# SCH_krunchcard_2025-07-20.net
KiCad netlist of a schematic drawn in EasyEDA
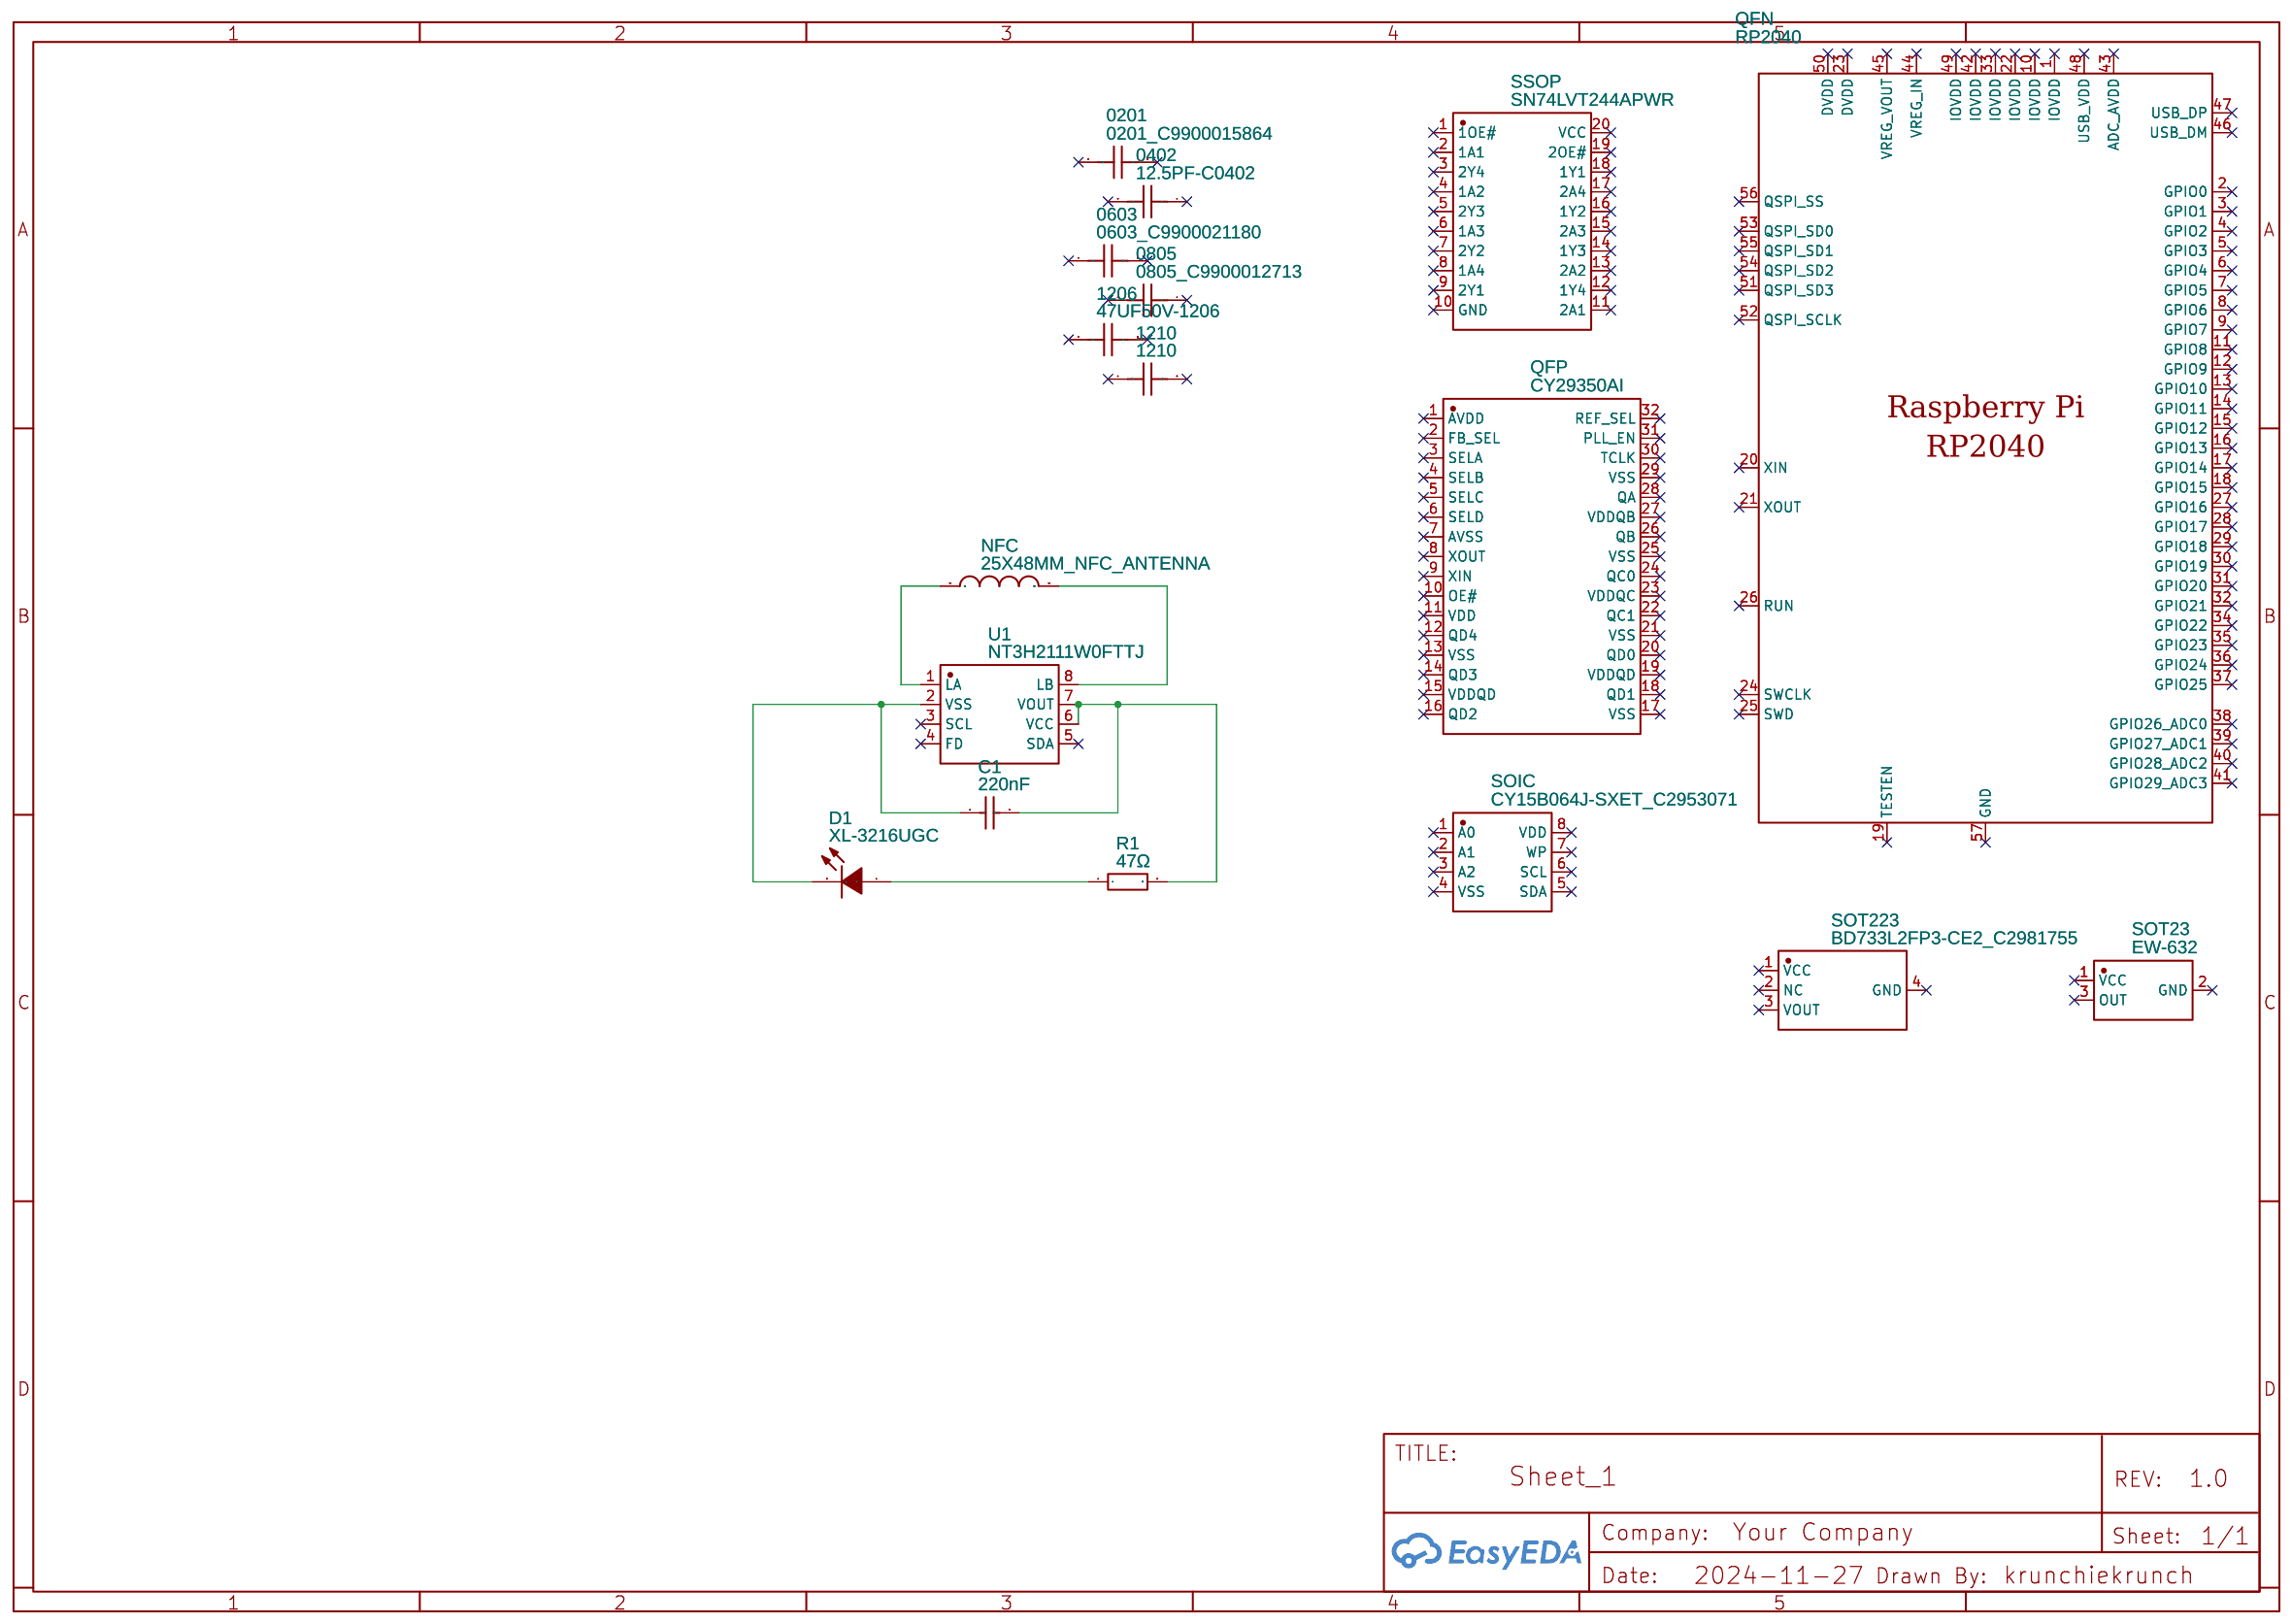
[diagram p0: schematic sheet]

(export (version "E")
  (design (tool "Eeschema 10.0.6"))
  (components
    (comp (ref "0201")
      (value "0201_C9900015864")
      (fields (field (name "Manufacturer Part") "0201"))
      (libsource (lib "") (part "0201_C9900015864"))
    )
    (comp (ref "0402")
      (value "12.5PF-C0402")
      (fields (field (name "Manufacturer Part") "12.5pF-C0402"))
      (libsource (lib "") (part "12.5PF-C0402"))
    )
    (comp (ref "0603")
      (value "0603_C9900021180")
      (fields (field (name "Manufacturer Part") "0603"))
      (libsource (lib "") (part "0603_C9900021180"))
    )
    (comp (ref "0805")
      (value "0805_C9900012713")
      (fields (field (name "Manufacturer Part") "0805"))
      (libsource (lib "") (part "0805_C9900012713"))
    )
    (comp (ref "1206")
      (value "47UF50V-1206")
      (fields (field (name "Manufacturer Part") "47uF50V-1206"))
      (libsource (lib "") (part "47UF50V-1206"))
    )
    (comp (ref "1210") (value "1210") (libsource (lib "") (part "1210")))
    (comp (ref "C1")
      (value "220nF")
      (fields
        (field (name "Manufacturer Part") "CC1206KKX7R9BB224")
        (field (name "Manufacturer") "YAGEO(国巨)")
      )
      (libsource (lib "") (part "CC1206KKX7R9BB224"))
    )
    (comp (ref "D1")
      (value "XL-3216UGC")
      (fields (field (name "Manufacturer") "XINGLIGHT(成兴光)"))
      (libsource (lib "") (part "XL-3216UGC"))
    )
    (comp (ref "NFC") (value "25X48MM_NFC_ANTENNA") (libsource (lib "") (part "25X48MM_NFC_ANTENNA")))
    (comp (ref "QFN")
      (value "RP2040")
      (fields (field (name "Manufacturer") "Raspberry Pi(树莓派)"))
      (libsource (lib "") (part "RP2040"))
    )
    (comp (ref "QFP")
      (value "CY29350AI")
      (fields (field (name "Manufacturer") "CYPRESS(赛普拉斯)"))
      (libsource (lib "") (part "CY29350AI"))
    )
    (comp (ref "R1")
      (value "47Ω")
      (fields (field (name "Manufacturer Part") "RS-06K470JT") (field (name "Manufacturer") "FH(风华)"))
      (libsource (lib "") (part "RS-06K470JT"))
    )
    (comp (ref "SOIC")
      (value "CY15B064J-SXET_C2953071")
      (fields
        (field (name "Manufacturer Part") "CY15B064J-SXET")
        (field (name "Manufacturer") "CYPRESS(赛普拉斯)")
      )
      (libsource (lib "") (part "CY15B064J-SXET_C2953071"))
    )
    (comp (ref "SOT23") (value "EW-632") (libsource (lib "") (part "EW-632")))
    (comp (ref "SOT223")
      (value "BD733L2FP3-CE2_C2981755")
      (fields (field (name "Manufacturer Part") "BD733L2FP3-CE2") (field (name "Manufacturer") "ROHM(罗姆)"))
      (libsource (lib "") (part "BD733L2FP3-CE2_C2981755"))
    )
    (comp (ref "SSOP")
      (value "SN74LVT244APWR")
      (fields (field (name "Manufacturer") "TI(德州仪器)"))
      (libsource (lib "") (part "SN74LVT244APWR"))
    )
    (comp (ref "U1")
      (value "NT3H2111W0FTTJ")
      (fields (field (name "Manufacturer") "NXP(恩智浦)"))
      (libsource (lib "") (part "NT3H2111W0FTTJ"))
    )
  )
  (nets
    (net (code "1") (name "Net-(D1-A)") (class "Default")
      (node (ref "D1") (pin "1") (pinfunction "A_1") (pintype "unspecified"))
      (node (ref "R1") (pin "1") (pinfunction "1_1") (pintype "input"))
    )
    (net (code "2") (name "Net-(D1-K)") (class "Default")
      (node (ref "C1") (pin "1") (pinfunction "1_1") (pintype "input"))
      (node (ref "D1") (pin "2") (pinfunction "K_2") (pintype "unspecified"))
      (node (ref "U1") (pin "2") (pinfunction "VSS_2") (pintype "unspecified"))
    )
    (net (code "3") (name "Net-(U1-LA)") (class "Default")
      (node (ref "NFC") (pin "P$1") (pinfunction "P$1_P$1") (pintype "bidirectional"))
      (node (ref "U1") (pin "1") (pinfunction "LA_1") (pintype "unspecified"))
    )
    (net (code "4") (name "Net-(U1-LB)") (class "Default")
      (node (ref "NFC") (pin "P$2") (pinfunction "P$2_P$2") (pintype "bidirectional"))
      (node (ref "U1") (pin "8") (pinfunction "LB_8") (pintype "unspecified"))
    )
    (net (code "5") (name "Net-(U1-VCC)") (class "Default")
      (node (ref "C1") (pin "2") (pinfunction "2_2") (pintype "input"))
      (node (ref "R1") (pin "2") (pinfunction "2_2") (pintype "input"))
      (node (ref "U1") (pin "6") (pinfunction "VCC_6") (pintype "unspecified"))
      (node (ref "U1") (pin "7") (pinfunction "VOUT_7") (pintype "unspecified"))
    )
    (net (code "6") (name "unconnected-(0201-Pad1)") (class "Default")
      (node (ref "0201") (pin "1") (pinfunction "1_1") (pintype "unspecified+no_connect"))
    )
    (net (code "7") (name "unconnected-(0201-Pad2)") (class "Default")
      (node (ref "0201") (pin "2") (pinfunction "2_2") (pintype "unspecified+no_connect"))
    )
    (net (code "8") (name "unconnected-(0402-Pad1)") (class "Default")
      (node (ref "0402") (pin "1") (pinfunction "1_1") (pintype "unspecified+no_connect"))
    )
    (net (code "9") (name "unconnected-(0402-Pad2)") (class "Default")
      (node (ref "0402") (pin "2") (pinfunction "2_2") (pintype "unspecified+no_connect"))
    )
    (net (code "10") (name "unconnected-(0603-Pad1)") (class "Default")
      (node (ref "0603") (pin "1") (pinfunction "1_1") (pintype "unspecified+no_connect"))
    )
    (net (code "11") (name "unconnected-(0603-Pad2)") (class "Default")
      (node (ref "0603") (pin "2") (pinfunction "2_2") (pintype "unspecified+no_connect"))
    )
    (net (code "12") (name "unconnected-(0805-Pad1)") (class "Default")
      (node (ref "0805") (pin "1") (pinfunction "1_1") (pintype "unspecified+no_connect"))
    )
    (net (code "13") (name "unconnected-(0805-Pad2)") (class "Default")
      (node (ref "0805") (pin "2") (pinfunction "2_2") (pintype "unspecified+no_connect"))
    )
    (net (code "14") (name "unconnected-(1206-Pad1)") (class "Default")
      (node (ref "1206") (pin "1") (pinfunction "1_1") (pintype "unspecified+no_connect"))
    )
    (net (code "15") (name "unconnected-(1206-Pad2)") (class "Default")
      (node (ref "1206") (pin "2") (pinfunction "2_2") (pintype "unspecified+no_connect"))
    )
    (net (code "16") (name "unconnected-(1210-Pad1)") (class "Default")
      (node (ref "1210") (pin "1") (pinfunction "1_1") (pintype "unspecified+no_connect"))
    )
    (net (code "17") (name "unconnected-(1210-Pad2)") (class "Default")
      (node (ref "1210") (pin "2") (pinfunction "2_2") (pintype "unspecified+no_connect"))
    )
    (net (code "18") (name "unconnected-(QFN-ADC_AVDD-Pad43)") (class "Default")
      (node (ref "QFN") (pin "43") (pinfunction "ADC_AVDD_43") (pintype "bidirectional+no_connect"))
    )
    (net (code "19") (name "unconnected-(QFN-DVDD-Pad23)") (class "Default")
      (node (ref "QFN") (pin "23") (pinfunction "DVDD_23") (pintype "bidirectional+no_connect"))
    )
    (net (code "20") (name "unconnected-(QFN-DVDD-Pad50)") (class "Default")
      (node (ref "QFN") (pin "50") (pinfunction "DVDD_50") (pintype "bidirectional+no_connect"))
    )
    (net (code "21") (name "unconnected-(QFN-GND-Pad57)") (class "Default")
      (node (ref "QFN") (pin "57") (pinfunction "GND_57") (pintype "bidirectional+no_connect"))
    )
    (net (code "22") (name "unconnected-(QFN-GPIO0-Pad2)") (class "Default")
      (node (ref "QFN") (pin "2") (pinfunction "GPIO0_2") (pintype "bidirectional+no_connect"))
    )
    (net (code "23") (name "unconnected-(QFN-GPIO1-Pad3)") (class "Default")
      (node (ref "QFN") (pin "3") (pinfunction "GPIO1_3") (pintype "bidirectional+no_connect"))
    )
    (net (code "24") (name "unconnected-(QFN-GPIO2-Pad4)") (class "Default")
      (node (ref "QFN") (pin "4") (pinfunction "GPIO2_4") (pintype "bidirectional+no_connect"))
    )
    (net (code "25") (name "unconnected-(QFN-GPIO3-Pad5)") (class "Default")
      (node (ref "QFN") (pin "5") (pinfunction "GPIO3_5") (pintype "bidirectional+no_connect"))
    )
    (net (code "26") (name "unconnected-(QFN-GPIO4-Pad6)") (class "Default")
      (node (ref "QFN") (pin "6") (pinfunction "GPIO4_6") (pintype "bidirectional+no_connect"))
    )
    (net (code "27") (name "unconnected-(QFN-GPIO5-Pad7)") (class "Default")
      (node (ref "QFN") (pin "7") (pinfunction "GPIO5_7") (pintype "bidirectional+no_connect"))
    )
    (net (code "28") (name "unconnected-(QFN-GPIO6-Pad8)") (class "Default")
      (node (ref "QFN") (pin "8") (pinfunction "GPIO6_8") (pintype "bidirectional+no_connect"))
    )
    (net (code "29") (name "unconnected-(QFN-GPIO7-Pad9)") (class "Default")
      (node (ref "QFN") (pin "9") (pinfunction "GPIO7_9") (pintype "bidirectional+no_connect"))
    )
    (net (code "30") (name "unconnected-(QFN-GPIO8-Pad11)") (class "Default")
      (node (ref "QFN") (pin "11") (pinfunction "GPIO8_11") (pintype "bidirectional+no_connect"))
    )
    (net (code "31") (name "unconnected-(QFN-GPIO9-Pad12)") (class "Default")
      (node (ref "QFN") (pin "12") (pinfunction "GPIO9_12") (pintype "bidirectional+no_connect"))
    )
    (net (code "32") (name "unconnected-(QFN-GPIO10-Pad13)") (class "Default")
      (node (ref "QFN") (pin "13") (pinfunction "GPIO10_13") (pintype "bidirectional+no_connect"))
    )
    (net (code "33") (name "unconnected-(QFN-GPIO11-Pad14)") (class "Default")
      (node (ref "QFN") (pin "14") (pinfunction "GPIO11_14") (pintype "bidirectional+no_connect"))
    )
    (net (code "34") (name "unconnected-(QFN-GPIO12-Pad15)") (class "Default")
      (node (ref "QFN") (pin "15") (pinfunction "GPIO12_15") (pintype "bidirectional+no_connect"))
    )
    (net (code "35") (name "unconnected-(QFN-GPIO13-Pad16)") (class "Default")
      (node (ref "QFN") (pin "16") (pinfunction "GPIO13_16") (pintype "bidirectional+no_connect"))
    )
    (net (code "36") (name "unconnected-(QFN-GPIO14-Pad17)") (class "Default")
      (node (ref "QFN") (pin "17") (pinfunction "GPIO14_17") (pintype "bidirectional+no_connect"))
    )
    (net (code "37") (name "unconnected-(QFN-GPIO15-Pad18)") (class "Default")
      (node (ref "QFN") (pin "18") (pinfunction "GPIO15_18") (pintype "bidirectional+no_connect"))
    )
    (net (code "38") (name "unconnected-(QFN-GPIO16-Pad27)") (class "Default")
      (node (ref "QFN") (pin "27") (pinfunction "GPIO16_27") (pintype "bidirectional+no_connect"))
    )
    (net (code "39") (name "unconnected-(QFN-GPIO17-Pad28)") (class "Default")
      (node (ref "QFN") (pin "28") (pinfunction "GPIO17_28") (pintype "bidirectional+no_connect"))
    )
    (net (code "40") (name "unconnected-(QFN-GPIO18-Pad29)") (class "Default")
      (node (ref "QFN") (pin "29") (pinfunction "GPIO18_29") (pintype "bidirectional+no_connect"))
    )
    (net (code "41") (name "unconnected-(QFN-GPIO19-Pad30)") (class "Default")
      (node (ref "QFN") (pin "30") (pinfunction "GPIO19_30") (pintype "bidirectional+no_connect"))
    )
    (net (code "42") (name "unconnected-(QFN-GPIO20-Pad31)") (class "Default")
      (node (ref "QFN") (pin "31") (pinfunction "GPIO20_31") (pintype "bidirectional+no_connect"))
    )
    (net (code "43") (name "unconnected-(QFN-GPIO21-Pad32)") (class "Default")
      (node (ref "QFN") (pin "32") (pinfunction "GPIO21_32") (pintype "bidirectional+no_connect"))
    )
    (net (code "44") (name "unconnected-(QFN-GPIO22-Pad34)") (class "Default")
      (node (ref "QFN") (pin "34") (pinfunction "GPIO22_34") (pintype "bidirectional+no_connect"))
    )
    (net (code "45") (name "unconnected-(QFN-GPIO23-Pad35)") (class "Default")
      (node (ref "QFN") (pin "35") (pinfunction "GPIO23_35") (pintype "bidirectional+no_connect"))
    )
    (net (code "46") (name "unconnected-(QFN-GPIO24-Pad36)") (class "Default")
      (node (ref "QFN") (pin "36") (pinfunction "GPIO24_36") (pintype "bidirectional+no_connect"))
    )
    (net (code "47") (name "unconnected-(QFN-GPIO25-Pad37)") (class "Default")
      (node (ref "QFN") (pin "37") (pinfunction "GPIO25_37") (pintype "bidirectional+no_connect"))
    )
    (net (code "48") (name "unconnected-(QFN-GPIO26_ADC0-Pad38)") (class "Default")
      (node (ref "QFN") (pin "38") (pinfunction "GPIO26_ADC0_38") (pintype "bidirectional+no_connect"))
    )
    (net (code "49") (name "unconnected-(QFN-GPIO27_ADC1-Pad39)") (class "Default")
      (node (ref "QFN") (pin "39") (pinfunction "GPIO27_ADC1_39") (pintype "bidirectional+no_connect"))
    )
    (net (code "50") (name "unconnected-(QFN-GPIO28_ADC2-Pad40)") (class "Default")
      (node (ref "QFN") (pin "40") (pinfunction "GPIO28_ADC2_40") (pintype "bidirectional+no_connect"))
    )
    (net (code "51") (name "unconnected-(QFN-GPIO29_ADC3-Pad41)") (class "Default")
      (node (ref "QFN") (pin "41") (pinfunction "GPIO29_ADC3_41") (pintype "bidirectional+no_connect"))
    )
    (net (code "52") (name "unconnected-(QFN-IOVDD-Pad1)") (class "Default")
      (node (ref "QFN") (pin "1") (pinfunction "IOVDD_1") (pintype "bidirectional+no_connect"))
    )
    (net (code "53") (name "unconnected-(QFN-IOVDD-Pad10)") (class "Default")
      (node (ref "QFN") (pin "10") (pinfunction "IOVDD_10") (pintype "bidirectional+no_connect"))
    )
    (net (code "54") (name "unconnected-(QFN-IOVDD-Pad22)") (class "Default")
      (node (ref "QFN") (pin "22") (pinfunction "IOVDD_22") (pintype "bidirectional+no_connect"))
    )
    (net (code "55") (name "unconnected-(QFN-IOVDD-Pad33)") (class "Default")
      (node (ref "QFN") (pin "33") (pinfunction "IOVDD_33") (pintype "bidirectional+no_connect"))
    )
    (net (code "56") (name "unconnected-(QFN-IOVDD-Pad42)") (class "Default")
      (node (ref "QFN") (pin "42") (pinfunction "IOVDD_42") (pintype "bidirectional+no_connect"))
    )
    (net (code "57") (name "unconnected-(QFN-IOVDD-Pad49)") (class "Default")
      (node (ref "QFN") (pin "49") (pinfunction "IOVDD_49") (pintype "bidirectional+no_connect"))
    )
    (net (code "58") (name "unconnected-(QFN-QSPI_SCLK-Pad52)") (class "Default")
      (node (ref "QFN") (pin "52") (pinfunction "QSPI_SCLK_52") (pintype "output+no_connect"))
    )
    (net (code "59") (name "unconnected-(QFN-QSPI_SD0-Pad53)") (class "Default")
      (node (ref "QFN") (pin "53") (pinfunction "QSPI_SD0_53") (pintype "bidirectional+no_connect"))
    )
    (net (code "60") (name "unconnected-(QFN-QSPI_SD1-Pad55)") (class "Default")
      (node (ref "QFN") (pin "55") (pinfunction "QSPI_SD1_55") (pintype "bidirectional+no_connect"))
    )
    (net (code "61") (name "unconnected-(QFN-QSPI_SD2-Pad54)") (class "Default")
      (node (ref "QFN") (pin "54") (pinfunction "QSPI_SD2_54") (pintype "bidirectional+no_connect"))
    )
    (net (code "62") (name "unconnected-(QFN-QSPI_SD3-Pad51)") (class "Default")
      (node (ref "QFN") (pin "51") (pinfunction "QSPI_SD3_51") (pintype "bidirectional+no_connect"))
    )
    (net (code "63") (name "unconnected-(QFN-QSPI_SS-Pad56)") (class "Default")
      (node (ref "QFN") (pin "56") (pinfunction "QSPI_SS_56") (pintype "bidirectional+no_connect"))
    )
    (net (code "64") (name "unconnected-(QFN-RUN-Pad26)") (class "Default")
      (node (ref "QFN") (pin "26") (pinfunction "RUN_26") (pintype "input+no_connect"))
    )
    (net (code "65") (name "unconnected-(QFN-SWCLK-Pad24)") (class "Default")
      (node (ref "QFN") (pin "24") (pinfunction "SWCLK_24") (pintype "output+no_connect"))
    )
    (net (code "66") (name "unconnected-(QFN-SWD-Pad25)") (class "Default")
      (node (ref "QFN") (pin "25") (pinfunction "SWD_25") (pintype "bidirectional+no_connect"))
    )
    (net (code "67") (name "unconnected-(QFN-TESTEN-Pad19)") (class "Default")
      (node (ref "QFN") (pin "19") (pinfunction "TESTEN_19") (pintype "unspecified+no_connect"))
    )
    (net (code "68") (name "unconnected-(QFN-USB_DM-Pad46)") (class "Default")
      (node (ref "QFN") (pin "46") (pinfunction "USB_DM_46") (pintype "bidirectional+no_connect"))
    )
    (net (code "69") (name "unconnected-(QFN-USB_DP-Pad47)") (class "Default")
      (node (ref "QFN") (pin "47") (pinfunction "USB_DP_47") (pintype "bidirectional+no_connect"))
    )
    (net (code "70") (name "unconnected-(QFN-USB_VDD-Pad48)") (class "Default")
      (node (ref "QFN") (pin "48") (pinfunction "USB_VDD_48") (pintype "bidirectional+no_connect"))
    )
    (net (code "71") (name "unconnected-(QFN-VREG_IN-Pad44)") (class "Default")
      (node (ref "QFN") (pin "44") (pinfunction "VREG_IN_44") (pintype "bidirectional+no_connect"))
    )
    (net (code "72") (name "unconnected-(QFN-VREG_VOUT-Pad45)") (class "Default")
      (node (ref "QFN") (pin "45") (pinfunction "VREG_VOUT_45") (pintype "bidirectional+no_connect"))
    )
    (net (code "73") (name "unconnected-(QFN-XIN-Pad20)") (class "Default")
      (node (ref "QFN") (pin "20") (pinfunction "XIN_20") (pintype "input+no_connect"))
    )
    (net (code "74") (name "unconnected-(QFN-XOUT-Pad21)") (class "Default")
      (node (ref "QFN") (pin "21") (pinfunction "XOUT_21") (pintype "unspecified+no_connect"))
    )
    (net (code "75") (name "unconnected-(QFP-AVDD-Pad1)") (class "Default")
      (node (ref "QFP") (pin "1") (pinfunction "AVDD_1") (pintype "unspecified+no_connect"))
    )
    (net (code "76") (name "unconnected-(QFP-AVSS-Pad7)") (class "Default")
      (node (ref "QFP") (pin "7") (pinfunction "AVSS_7") (pintype "unspecified+no_connect"))
    )
    (net (code "77") (name "unconnected-(QFP-FB_SEL-Pad2)") (class "Default")
      (node (ref "QFP") (pin "2") (pinfunction "FB_SEL_2") (pintype "unspecified+no_connect"))
    )
    (net (code "78") (name "unconnected-(QFP-OE#-Pad10)") (class "Default")
      (node (ref "QFP") (pin "10") (pinfunction "OE#_10") (pintype "unspecified+no_connect"))
    )
    (net (code "79") (name "unconnected-(QFP-PLL_EN-Pad31)") (class "Default")
      (node (ref "QFP") (pin "31") (pinfunction "PLL_EN_31") (pintype "unspecified+no_connect"))
    )
    (net (code "80") (name "unconnected-(QFP-QA-Pad28)") (class "Default")
      (node (ref "QFP") (pin "28") (pinfunction "QA_28") (pintype "unspecified+no_connect"))
    )
    (net (code "81") (name "unconnected-(QFP-QB-Pad26)") (class "Default")
      (node (ref "QFP") (pin "26") (pinfunction "QB_26") (pintype "unspecified+no_connect"))
    )
    (net (code "82") (name "unconnected-(QFP-QC0-Pad24)") (class "Default")
      (node (ref "QFP") (pin "24") (pinfunction "QC0_24") (pintype "unspecified+no_connect"))
    )
    (net (code "83") (name "unconnected-(QFP-QC1-Pad22)") (class "Default")
      (node (ref "QFP") (pin "22") (pinfunction "QC1_22") (pintype "unspecified+no_connect"))
    )
    (net (code "84") (name "unconnected-(QFP-QD0-Pad20)") (class "Default")
      (node (ref "QFP") (pin "20") (pinfunction "QD0_20") (pintype "unspecified+no_connect"))
    )
    (net (code "85") (name "unconnected-(QFP-QD1-Pad18)") (class "Default")
      (node (ref "QFP") (pin "18") (pinfunction "QD1_18") (pintype "unspecified+no_connect"))
    )
    (net (code "86") (name "unconnected-(QFP-QD2-Pad16)") (class "Default")
      (node (ref "QFP") (pin "16") (pinfunction "QD2_16") (pintype "unspecified+no_connect"))
    )
    (net (code "87") (name "unconnected-(QFP-QD3-Pad14)") (class "Default")
      (node (ref "QFP") (pin "14") (pinfunction "QD3_14") (pintype "unspecified+no_connect"))
    )
    (net (code "88") (name "unconnected-(QFP-QD4-Pad12)") (class "Default")
      (node (ref "QFP") (pin "12") (pinfunction "QD4_12") (pintype "unspecified+no_connect"))
    )
    (net (code "89") (name "unconnected-(QFP-REF_SEL-Pad32)") (class "Default")
      (node (ref "QFP") (pin "32") (pinfunction "REF_SEL_32") (pintype "unspecified+no_connect"))
    )
    (net (code "90") (name "unconnected-(QFP-SELA-Pad3)") (class "Default")
      (node (ref "QFP") (pin "3") (pinfunction "SELA_3") (pintype "unspecified+no_connect"))
    )
    (net (code "91") (name "unconnected-(QFP-SELB-Pad4)") (class "Default")
      (node (ref "QFP") (pin "4") (pinfunction "SELB_4") (pintype "unspecified+no_connect"))
    )
    (net (code "92") (name "unconnected-(QFP-SELC-Pad5)") (class "Default")
      (node (ref "QFP") (pin "5") (pinfunction "SELC_5") (pintype "unspecified+no_connect"))
    )
    (net (code "93") (name "unconnected-(QFP-SELD-Pad6)") (class "Default")
      (node (ref "QFP") (pin "6") (pinfunction "SELD_6") (pintype "unspecified+no_connect"))
    )
    (net (code "94") (name "unconnected-(QFP-TCLK-Pad30)") (class "Default")
      (node (ref "QFP") (pin "30") (pinfunction "TCLK_30") (pintype "unspecified+no_connect"))
    )
    (net (code "95") (name "unconnected-(QFP-VDD-Pad11)") (class "Default")
      (node (ref "QFP") (pin "11") (pinfunction "VDD_11") (pintype "unspecified+no_connect"))
    )
    (net (code "96") (name "unconnected-(QFP-VDDQB-Pad27)") (class "Default")
      (node (ref "QFP") (pin "27") (pinfunction "VDDQB_27") (pintype "unspecified+no_connect"))
    )
    (net (code "97") (name "unconnected-(QFP-VDDQC-Pad23)") (class "Default")
      (node (ref "QFP") (pin "23") (pinfunction "VDDQC_23") (pintype "unspecified+no_connect"))
    )
    (net (code "98") (name "unconnected-(QFP-VDDQD-Pad15)") (class "Default")
      (node (ref "QFP") (pin "15") (pinfunction "VDDQD_15") (pintype "unspecified+no_connect"))
    )
    (net (code "99") (name "unconnected-(QFP-VDDQD-Pad19)") (class "Default")
      (node (ref "QFP") (pin "19") (pinfunction "VDDQD_19") (pintype "unspecified+no_connect"))
    )
    (net (code "100") (name "unconnected-(QFP-VSS-Pad13)") (class "Default")
      (node (ref "QFP") (pin "13") (pinfunction "VSS_13") (pintype "unspecified+no_connect"))
    )
    (net (code "101") (name "unconnected-(QFP-VSS-Pad17)") (class "Default")
      (node (ref "QFP") (pin "17") (pinfunction "VSS_17") (pintype "unspecified+no_connect"))
    )
    (net (code "102") (name "unconnected-(QFP-VSS-Pad21)") (class "Default")
      (node (ref "QFP") (pin "21") (pinfunction "VSS_21") (pintype "unspecified+no_connect"))
    )
    (net (code "103") (name "unconnected-(QFP-VSS-Pad25)") (class "Default")
      (node (ref "QFP") (pin "25") (pinfunction "VSS_25") (pintype "unspecified+no_connect"))
    )
    (net (code "104") (name "unconnected-(QFP-VSS-Pad29)") (class "Default")
      (node (ref "QFP") (pin "29") (pinfunction "VSS_29") (pintype "unspecified+no_connect"))
    )
    (net (code "105") (name "unconnected-(QFP-XIN-Pad9)") (class "Default")
      (node (ref "QFP") (pin "9") (pinfunction "XIN_9") (pintype "unspecified+no_connect"))
    )
    (net (code "106") (name "unconnected-(QFP-XOUT-Pad8)") (class "Default")
      (node (ref "QFP") (pin "8") (pinfunction "XOUT_8") (pintype "unspecified+no_connect"))
    )
    (net (code "107") (name "unconnected-(SOIC-A0-Pad1)") (class "Default")
      (node (ref "SOIC") (pin "1") (pinfunction "A0_1") (pintype "unspecified+no_connect"))
    )
    (net (code "108") (name "unconnected-(SOIC-A1-Pad2)") (class "Default")
      (node (ref "SOIC") (pin "2") (pinfunction "A1_2") (pintype "unspecified+no_connect"))
    )
    (net (code "109") (name "unconnected-(SOIC-A2-Pad3)") (class "Default")
      (node (ref "SOIC") (pin "3") (pinfunction "A2_3") (pintype "unspecified+no_connect"))
    )
    (net (code "110") (name "unconnected-(SOIC-SCL-Pad6)") (class "Default")
      (node (ref "SOIC") (pin "6") (pinfunction "SCL_6") (pintype "unspecified+no_connect"))
    )
    (net (code "111") (name "unconnected-(SOIC-SDA-Pad5)") (class "Default")
      (node (ref "SOIC") (pin "5") (pinfunction "SDA_5") (pintype "unspecified+no_connect"))
    )
    (net (code "112") (name "unconnected-(SOIC-VDD-Pad8)") (class "Default")
      (node (ref "SOIC") (pin "8") (pinfunction "VDD_8") (pintype "unspecified+no_connect"))
    )
    (net (code "113") (name "unconnected-(SOIC-VSS-Pad4)") (class "Default")
      (node (ref "SOIC") (pin "4") (pinfunction "VSS_4") (pintype "unspecified+no_connect"))
    )
    (net (code "114") (name "unconnected-(SOIC-WP-Pad7)") (class "Default")
      (node (ref "SOIC") (pin "7") (pinfunction "WP_7") (pintype "unspecified+no_connect"))
    )
    (net (code "115") (name "unconnected-(SOT23-GND-Pad2)") (class "Default")
      (node (ref "SOT23") (pin "2") (pinfunction "GND_2") (pintype "unspecified+no_connect"))
    )
    (net (code "116") (name "unconnected-(SOT23-OUT-Pad3)") (class "Default")
      (node (ref "SOT23") (pin "3") (pinfunction "OUT_3") (pintype "unspecified+no_connect"))
    )
    (net (code "117") (name "unconnected-(SOT23-VCC-Pad1)") (class "Default")
      (node (ref "SOT23") (pin "1") (pinfunction "VCC_1") (pintype "unspecified+no_connect"))
    )
    (net (code "118") (name "unconnected-(SOT223-GND-Pad4)") (class "Default")
      (node (ref "SOT223") (pin "4") (pinfunction "GND_4") (pintype "unspecified+no_connect"))
    )
    (net (code "119") (name "unconnected-(SOT223-NC-Pad2)") (class "Default")
      (node (ref "SOT223") (pin "2") (pinfunction "NC_2") (pintype "unspecified+no_connect"))
    )
    (net (code "120") (name "unconnected-(SOT223-VCC-Pad1)") (class "Default")
      (node (ref "SOT223") (pin "1") (pinfunction "VCC_1") (pintype "unspecified+no_connect"))
    )
    (net (code "121") (name "unconnected-(SOT223-VOUT-Pad3)") (class "Default")
      (node (ref "SOT223") (pin "3") (pinfunction "VOUT_3") (pintype "unspecified+no_connect"))
    )
    (net (code "122") (name "unconnected-(SSOP-1A1-Pad2)") (class "Default")
      (node (ref "SSOP") (pin "2") (pinfunction "1A1_2") (pintype "unspecified+no_connect"))
    )
    (net (code "123") (name "unconnected-(SSOP-1A2-Pad4)") (class "Default")
      (node (ref "SSOP") (pin "4") (pinfunction "1A2_4") (pintype "unspecified+no_connect"))
    )
    (net (code "124") (name "unconnected-(SSOP-1A3-Pad6)") (class "Default")
      (node (ref "SSOP") (pin "6") (pinfunction "1A3_6") (pintype "unspecified+no_connect"))
    )
    (net (code "125") (name "unconnected-(SSOP-1A4-Pad8)") (class "Default")
      (node (ref "SSOP") (pin "8") (pinfunction "1A4_8") (pintype "unspecified+no_connect"))
    )
    (net (code "126") (name "unconnected-(SSOP-1OE#-Pad1)") (class "Default")
      (node (ref "SSOP") (pin "1") (pinfunction "1OE#_1") (pintype "unspecified+no_connect"))
    )
    (net (code "127") (name "unconnected-(SSOP-1Y1-Pad18)") (class "Default")
      (node (ref "SSOP") (pin "18") (pinfunction "1Y1_18") (pintype "unspecified+no_connect"))
    )
    (net (code "128") (name "unconnected-(SSOP-1Y2-Pad16)") (class "Default")
      (node (ref "SSOP") (pin "16") (pinfunction "1Y2_16") (pintype "unspecified+no_connect"))
    )
    (net (code "129") (name "unconnected-(SSOP-1Y3-Pad14)") (class "Default")
      (node (ref "SSOP") (pin "14") (pinfunction "1Y3_14") (pintype "unspecified+no_connect"))
    )
    (net (code "130") (name "unconnected-(SSOP-1Y4-Pad12)") (class "Default")
      (node (ref "SSOP") (pin "12") (pinfunction "1Y4_12") (pintype "unspecified+no_connect"))
    )
    (net (code "131") (name "unconnected-(SSOP-2A1-Pad11)") (class "Default")
      (node (ref "SSOP") (pin "11") (pinfunction "2A1_11") (pintype "unspecified+no_connect"))
    )
    (net (code "132") (name "unconnected-(SSOP-2A2-Pad13)") (class "Default")
      (node (ref "SSOP") (pin "13") (pinfunction "2A2_13") (pintype "unspecified+no_connect"))
    )
    (net (code "133") (name "unconnected-(SSOP-2A3-Pad15)") (class "Default")
      (node (ref "SSOP") (pin "15") (pinfunction "2A3_15") (pintype "unspecified+no_connect"))
    )
    (net (code "134") (name "unconnected-(SSOP-2A4-Pad17)") (class "Default")
      (node (ref "SSOP") (pin "17") (pinfunction "2A4_17") (pintype "unspecified+no_connect"))
    )
    (net (code "135") (name "unconnected-(SSOP-2OE#-Pad19)") (class "Default")
      (node (ref "SSOP") (pin "19") (pinfunction "2OE#_19") (pintype "unspecified+no_connect"))
    )
    (net (code "136") (name "unconnected-(SSOP-2Y1-Pad9)") (class "Default")
      (node (ref "SSOP") (pin "9") (pinfunction "2Y1_9") (pintype "unspecified+no_connect"))
    )
    (net (code "137") (name "unconnected-(SSOP-2Y2-Pad7)") (class "Default")
      (node (ref "SSOP") (pin "7") (pinfunction "2Y2_7") (pintype "unspecified+no_connect"))
    )
    (net (code "138") (name "unconnected-(SSOP-2Y3-Pad5)") (class "Default")
      (node (ref "SSOP") (pin "5") (pinfunction "2Y3_5") (pintype "unspecified+no_connect"))
    )
    (net (code "139") (name "unconnected-(SSOP-2Y4-Pad3)") (class "Default")
      (node (ref "SSOP") (pin "3") (pinfunction "2Y4_3") (pintype "unspecified+no_connect"))
    )
    (net (code "140") (name "unconnected-(SSOP-GND-Pad10)") (class "Default")
      (node (ref "SSOP") (pin "10") (pinfunction "GND_10") (pintype "unspecified+no_connect"))
    )
    (net (code "141") (name "unconnected-(SSOP-VCC-Pad20)") (class "Default")
      (node (ref "SSOP") (pin "20") (pinfunction "VCC_20") (pintype "unspecified+no_connect"))
    )
    (net (code "142") (name "unconnected-(U1-FD-Pad4)") (class "Default")
      (node (ref "U1") (pin "4") (pinfunction "FD_4") (pintype "unspecified+no_connect"))
    )
    (net (code "143") (name "unconnected-(U1-SCL-Pad3)") (class "Default")
      (node (ref "U1") (pin "3") (pinfunction "SCL_3") (pintype "unspecified+no_connect"))
    )
    (net (code "144") (name "unconnected-(U1-SDA-Pad5)") (class "Default")
      (node (ref "U1") (pin "5") (pinfunction "SDA_5") (pintype "unspecified+no_connect"))
    )
  )
)
